# ldr.net
KiCad netlist of a schematic drawn in EAGLE
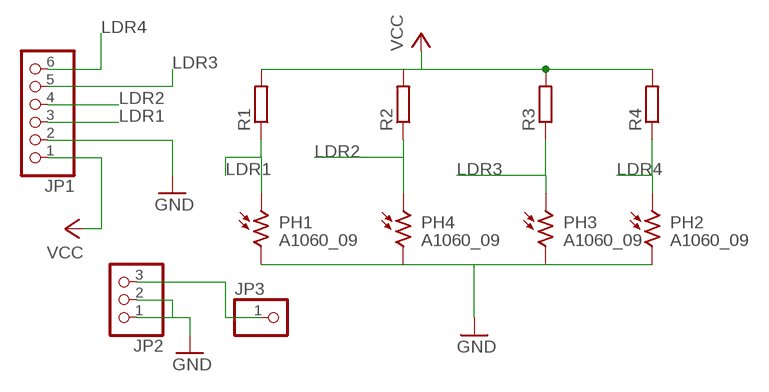
[diagram p0: schematic, sheet 1]

(export (version "E")
  (design (tool "Eeschema 10.0.6"))
  (components
    (comp (ref "JP1")
      (value "PINHD-1X6CB")
      (footprint "eagle-import:1X06-CLEANBIG")
      (libsource (lib "eagle-import") (part "PINHD-1X6CB"))
    )
    (comp (ref "JP2")
      (value "PINHD-1X3CB")
      (footprint "eagle-import:1X03-CLEANBIG")
      (libsource (lib "eagle-import") (part "PINHD-1X3CB"))
    )
    (comp (ref "JP3")
      (value "PINHD-1X1CB")
      (footprint "eagle-import:1X01-CLEANBIG")
      (libsource (lib "eagle-import") (part "PINHD-1X1CB"))
    )
    (comp (ref "PH1")
      (value "A1060_09")
      (footprint "eagle-import:T0-46-A10XX")
      (libsource (lib "eagle-import") (part "A1060_09"))
    )
    (comp (ref "PH2")
      (value "A1060_09")
      (footprint "eagle-import:T0-46-A10XX")
      (libsource (lib "eagle-import") (part "A1060_09"))
    )
    (comp (ref "PH3")
      (value "A1060_09")
      (footprint "eagle-import:T0-46-A10XX")
      (libsource (lib "eagle-import") (part "A1060_09"))
    )
    (comp (ref "PH4")
      (value "A1060_09")
      (footprint "eagle-import:T0-46-A10XX")
      (libsource (lib "eagle-import") (part "A1060_09"))
    )
    (comp (ref "R1")
      (value "R-EU_0207/10")
      (footprint "eagle-import:0207_10")
      (libsource (lib "eagle-import") (part "R-EU_0207/10"))
    )
    (comp (ref "R2")
      (value "R-EU_0207/10")
      (footprint "eagle-import:0207_10")
      (libsource (lib "eagle-import") (part "R-EU_0207/10"))
    )
    (comp (ref "R3")
      (value "R-EU_0207/10")
      (footprint "eagle-import:0207_10")
      (libsource (lib "eagle-import") (part "R-EU_0207/10"))
    )
    (comp (ref "R4")
      (value "R-EU_0207/10")
      (footprint "eagle-import:0207_10")
      (libsource (lib "eagle-import") (part "R-EU_0207/10"))
    )
  )
  (nets
    (net (code "1") (name "/LDR1") (class "Default")
      (node (ref "JP1") (pin "3") (pinfunction "3_3") (pintype "passive"))
      (node (ref "PH1") (pin "1") (pinfunction "1_1") (pintype "passive"))
      (node (ref "R1") (pin "1") (pinfunction "1_1") (pintype "passive"))
    )
    (net (code "2") (name "/LDR2") (class "Default")
      (node (ref "JP1") (pin "4") (pinfunction "4_4") (pintype "passive"))
      (node (ref "PH4") (pin "1") (pinfunction "1_1") (pintype "passive"))
      (node (ref "R2") (pin "1") (pinfunction "1_1") (pintype "passive"))
    )
    (net (code "3") (name "/LDR3") (class "Default")
      (node (ref "JP1") (pin "5") (pinfunction "5_5") (pintype "passive"))
      (node (ref "PH3") (pin "1") (pinfunction "1_1") (pintype "passive"))
      (node (ref "R3") (pin "1") (pinfunction "1_1") (pintype "passive"))
    )
    (net (code "4") (name "/LDR4") (class "Default")
      (node (ref "JP1") (pin "6") (pinfunction "6_6") (pintype "passive"))
      (node (ref "PH2") (pin "1") (pinfunction "1_1") (pintype "passive"))
      (node (ref "R4") (pin "1") (pinfunction "1_1") (pintype "passive"))
    )
    (net (code "5") (name "GND") (class "Default")
      (node (ref "JP1") (pin "2") (pinfunction "2_2") (pintype "passive"))
      (node (ref "JP2") (pin "1") (pinfunction "1_1") (pintype "passive"))
      (node (ref "JP2") (pin "2") (pinfunction "2_2") (pintype "passive"))
      (node (ref "PH1") (pin "2") (pinfunction "2_2") (pintype "passive"))
      (node (ref "PH2") (pin "2") (pinfunction "2_2") (pintype "passive"))
      (node (ref "PH3") (pin "2") (pinfunction "2_2") (pintype "passive"))
      (node (ref "PH4") (pin "2") (pinfunction "2_2") (pintype "passive"))
    )
    (net (code "6") (name "Net-(JP2-Pad3)") (class "Default")
      (node (ref "JP2") (pin "3") (pinfunction "3_3") (pintype "passive"))
      (node (ref "JP3") (pin "1") (pinfunction "1_1") (pintype "passive"))
    )
    (net (code "7") (name "VCC") (class "Default")
      (node (ref "JP1") (pin "1") (pinfunction "1_1") (pintype "passive"))
      (node (ref "R1") (pin "2") (pinfunction "2_2") (pintype "passive"))
      (node (ref "R2") (pin "2") (pinfunction "2_2") (pintype "passive"))
      (node (ref "R3") (pin "2") (pinfunction "2_2") (pintype "passive"))
      (node (ref "R4") (pin "2") (pinfunction "2_2") (pintype "passive"))
    )
  )
)
